# top.net
KiCad netlist of a schematic drawn in Altium Designer
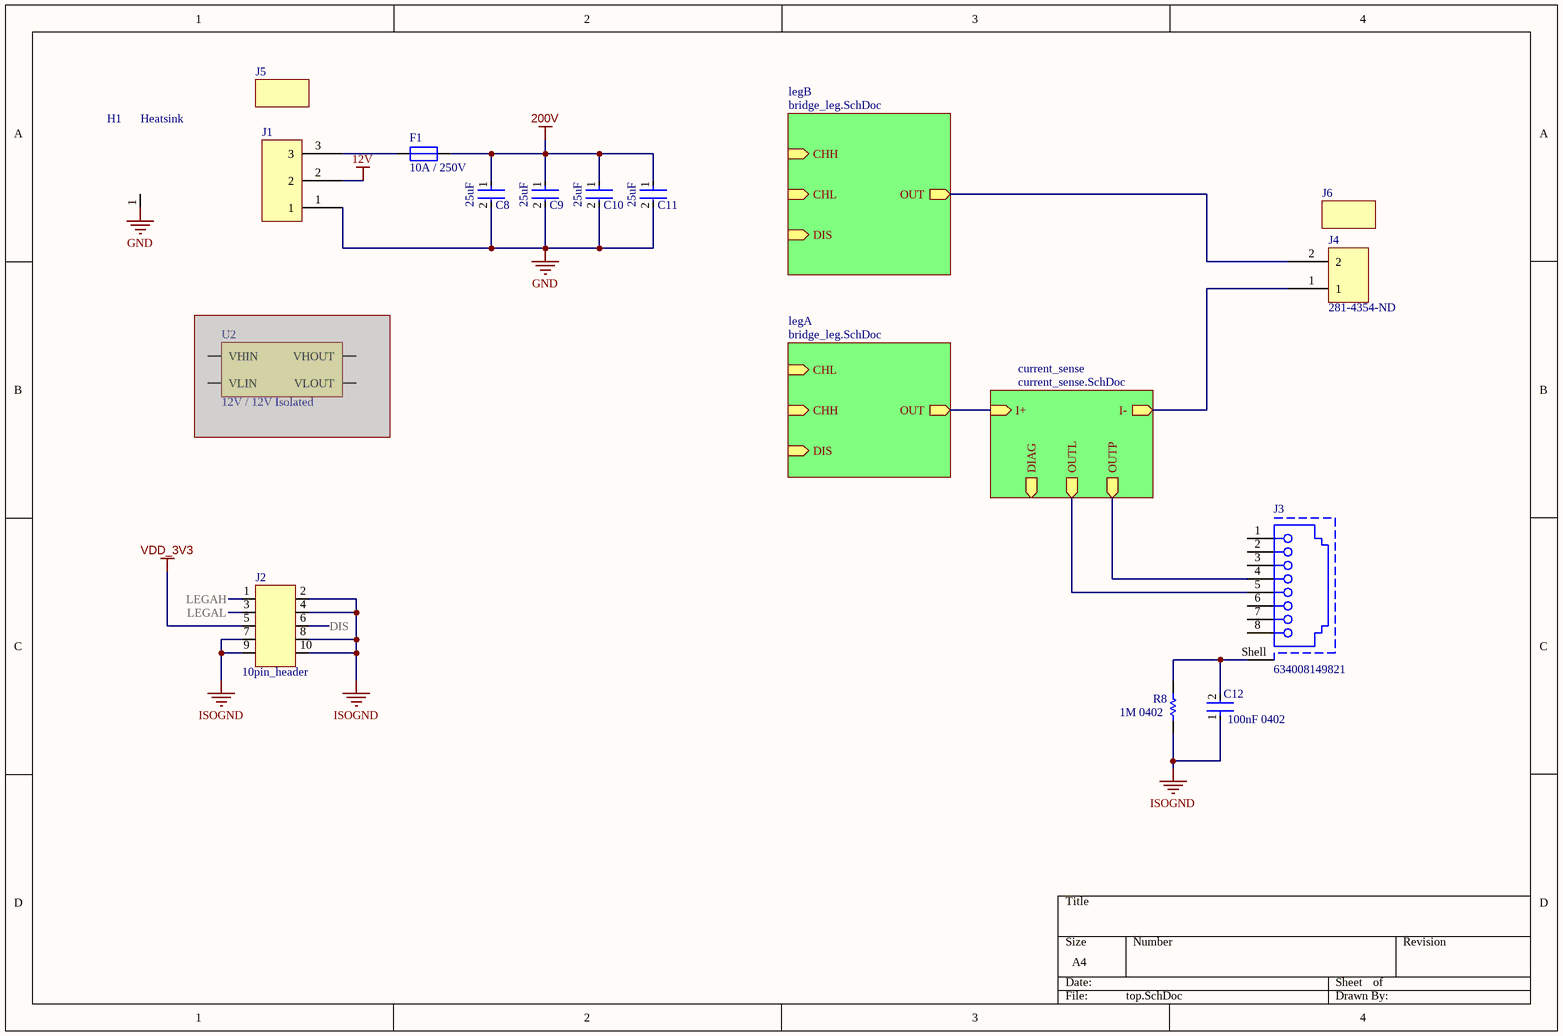
[diagram p0: top.SchDoc]

(export (version "E")
  (design (tool "Eeschema 10.0.6"))
  (components
    (comp (ref "C8")
      (value "25uF")
      (footprint "film_cap_50uF")
      (description "FIlm Cap 25uF 450V")
      (fields (field (name "VOLTAGE") "50V") (field (name "TOLERANCE") "5%"))
      (libsource (lib "mdriver2_control") (part "b4654b650e69147ec39a6b967a45e02"))
    )
    (comp (ref "C9")
      (value "25uF")
      (footprint "film_cap_50uF")
      (description "FIlm Cap 25uF 450V")
      (fields (field (name "VOLTAGE") "50V") (field (name "TOLERANCE") "5%"))
      (libsource (lib "mdriver2_control") (part "b4654b650e69147ec39a6b967a45e02"))
    )
    (comp (ref "C10")
      (value "25uF")
      (footprint "film_cap_50uF")
      (description "FIlm Cap 25uF 450V")
      (fields (field (name "VOLTAGE") "50V") (field (name "TOLERANCE") "5%"))
      (libsource (lib "mdriver2_control") (part "b4654b650e69147ec39a6b967a45e02"))
    )
    (comp (ref "C11")
      (value "25uF")
      (footprint "film_cap_50uF")
      (description "FIlm Cap 25uF 450V")
      (fields (field (name "VOLTAGE") "50V") (field (name "TOLERANCE") "5%"))
      (libsource (lib "mdriver2_control") (part "b4654b650e69147ec39a6b967a45e02"))
    )
    (comp (ref "C12")
      (value "100nF 0402")
      (footprint "CAP 0402_1005 RF")
      (description "MLCC 0402 100nF")
      (fields (field (name "VOLTAGE") "50V") (field (name "TOLERANCE") "5%"))
      (libsource (lib "mdriver2_control") (part "b4654b650e69147ec39a6b967a45e02"))
    )
    (comp (ref "F1")
      (value "10A / 250V")
      (footprint "fuseholder_5mm_20mm")
      (description "Fuse Holder 5mm/20mm")
      (libsource (lib "general_purpose_lib") (part "fuse"))
    )
    (comp (ref "H1")
      (value "Heatsink")
      (footprint "HEATSINK2")
      (description "HEATSINK TO247 W/CLIP 75MM")
      (libsource (lib "general_purpose_lib") (part "heatsink_2"))
    )
    (comp (ref "J1")
      (value "20A Socket 3Pin")
      (footprint "weidmuller_3p_20A")
      (libsource (lib "coil_driver_lib") (part "wuerth_connector_straight_30_20A_691311500103"))
    )
    (comp (ref "J2")
      (value "10pin_header")
      (footprint "header_10")
      (description "Pin header male 2x5 2.54mm")
      (libsource (lib "general_purpose_lib") (part "10pin_header"))
    )
    (comp (ref "J3")
      (value "634008149821")
      (footprint "634008149821")
      (libsource (lib "Components - 28.07.25 - 15.35") (part "CMP-1502-01719-2"))
    )
    (comp (ref "J4")
      (value "weidmuller_20A_2p_f")
      (footprint "weidmuller_19A_2p_m")
      (description "Connector Block 19A Male Receptor")
      (fields (field (name "SUPPLIER PART NUMBER 1") "281-4354-ND"))
      (libsource (lib "coil_driver_lib") (part "weidmuller_20A_2p_f"))
    )
    (comp (ref "J5")
      (value "20A Power Plug 3 Pin")
      (libsource (lib "general_purpose_lib") (part "weidmuller_3pin_male"))
    )
    (comp (ref "J6")
      (value "20A Power Plug 2 Pin")
      (libsource (lib "general_purpose_lib") (part "weidmuller_3pin_male"))
    )
    (comp (ref "R8")
      (value "1M 0402")
      (footprint "RES 0402_1005")
      (description "Resistor 10MOhm 0603")
      (fields (field (name "PUBLISHER") "Altium Limited"))
      (libsource (lib "Miscellaneous Devices") (part "Res1"))
    )
    (comp (ref "U2")
      (value "12V / 12V Isolated")
      (footprint "gatesupply")
      (libsource (lib "general_purpose_lib") (part "gatesupply"))
    )
  )
  (nets
    (net (code "6") (name "/DIS") (class "Default") (node (ref "J2") (pin "6") (pintype "passive")))
    (net (code "9") (name "/I-") (class "Default")
      (node (ref "J4") (pin "1") (pinfunction "1_1") (pintype "passive"))
    )
    (net (code "10") (name "/LEGAH") (class "Default") (node (ref "J2") (pin "1") (pintype "passive")))
    (net (code "11") (name "/LEGAL") (class "Default") (node (ref "J2") (pin "3") (pintype "passive")))
    (net (code "12") (name "/OUT") (class "Default")
      (node (ref "J4") (pin "2") (pinfunction "2_2") (pintype "passive"))
    )
    (net (code "13") (name "/OUTL") (class "Default")
      (node (ref "J3") (pin "5") (pinfunction "5_5") (pintype "passive"))
    )
    (net (code "14") (name "/OUTP") (class "Default")
      (node (ref "J3") (pin "4") (pinfunction "4_4") (pintype "passive"))
    )
    (net (code "16") (name "12V") (class "Default")
      (node (ref "J1") (pin "2") (pinfunction "2_2") (pintype "passive"))
    )
    (net (code "17") (name "200V") (class "Default")
      (node (ref "C10") (pin "1") (pinfunction "1_1") (pintype "passive"))
      (node (ref "C11") (pin "1") (pinfunction "1_1") (pintype "passive"))
      (node (ref "C8") (pin "1") (pinfunction "1_1") (pintype "passive"))
      (node (ref "C9") (pin "1") (pinfunction "1_1") (pintype "passive"))
      (node (ref "F1") (pin "1") (pinfunction "1_1") (pintype "passive"))
    )
    (net (code "18") (name "GND") (class "Default")
      (node (ref "C10") (pin "2") (pinfunction "2_2") (pintype "passive"))
      (node (ref "C11") (pin "2") (pinfunction "2_2") (pintype "passive"))
      (node (ref "C8") (pin "2") (pinfunction "2_2") (pintype "passive"))
      (node (ref "C9") (pin "2") (pinfunction "2_2") (pintype "passive"))
      (node (ref "H1") (pin "1") (pinfunction "1_1") (pintype "passive"))
      (node (ref "J1") (pin "1") (pinfunction "1_1") (pintype "passive"))
    )
    (net (code "19") (name "ISOGND") (class "Default")
      (node (ref "C12") (pin "1") (pinfunction "1_1") (pintype "passive"))
      (node (ref "J2") (pin "10") (pintype "passive"))
      (node (ref "J2") (pin "2") (pintype "passive"))
      (node (ref "J2") (pin "4") (pintype "passive"))
      (node (ref "J2") (pin "7") (pintype "passive"))
      (node (ref "J2") (pin "8") (pintype "passive"))
      (node (ref "J2") (pin "9") (pintype "passive"))
      (node (ref "R8") (pin "2") (pinfunction "2_2") (pintype "passive"))
    )
    (net (code "20") (name "Net-(C12-Pad2)") (class "Default")
      (node (ref "C12") (pin "2") (pinfunction "2_2") (pintype "passive"))
      (node (ref "J3") (pin "Shell") (pinfunction "Shell_Shell") (pintype "passive"))
      (node (ref "R8") (pin "1") (pinfunction "1_1") (pintype "passive"))
    )
    (net (code "21") (name "Net-(F1-Pad2)") (class "Default")
      (node (ref "F1") (pin "2") (pinfunction "2_2") (pintype "passive"))
      (node (ref "J1") (pin "3") (pinfunction "3_3") (pintype "passive"))
    )
    (net (code "22") (name "VDD_3V3") (class "Default") (node (ref "J2") (pin "5") (pintype "passive")))
    (net (code "23") (name "unconnected-(J3-Pad1)") (class "Default")
      (node (ref "J3") (pin "1") (pinfunction "1_1") (pintype "passive"))
    )
    (net (code "24") (name "unconnected-(J3-Pad2)") (class "Default")
      (node (ref "J3") (pin "2") (pinfunction "2_2") (pintype "passive"))
    )
    (net (code "25") (name "unconnected-(J3-Pad3)") (class "Default")
      (node (ref "J3") (pin "3") (pinfunction "3_3") (pintype "passive"))
    )
    (net (code "26") (name "unconnected-(J3-Pad6)") (class "Default")
      (node (ref "J3") (pin "6") (pinfunction "6_6") (pintype "passive"))
    )
    (net (code "27") (name "unconnected-(J3-Pad7)") (class "Default")
      (node (ref "J3") (pin "7") (pinfunction "7_7") (pintype "passive"))
    )
    (net (code "28") (name "unconnected-(J3-Pad8)") (class "Default")
      (node (ref "J3") (pin "8") (pinfunction "8_8") (pintype "passive"))
    )
    (net (code "29") (name "unconnected-(U2-VHIN-Pad3)") (class "Default")
      (node (ref "U2") (pin "3") (pinfunction "VHIN_3") (pintype "passive"))
    )
    (net (code "30") (name "unconnected-(U2-VHOUT-Pad8)") (class "Default")
      (node (ref "U2") (pin "8") (pinfunction "VHOUT_8") (pintype "passive"))
    )
    (net (code "31") (name "unconnected-(U2-VLIN-Pad1)") (class "Default")
      (node (ref "U2") (pin "1") (pinfunction "VLIN_1") (pintype "passive"))
    )
    (net (code "32") (name "unconnected-(U2-VLOUT-Pad7)") (class "Default")
      (node (ref "U2") (pin "7") (pinfunction "VLOUT_7") (pintype "passive"))
    )
  )
)
